# SCH_SrProj_v1_2.net
KiCad netlist of a schematic drawn in EasyEDA
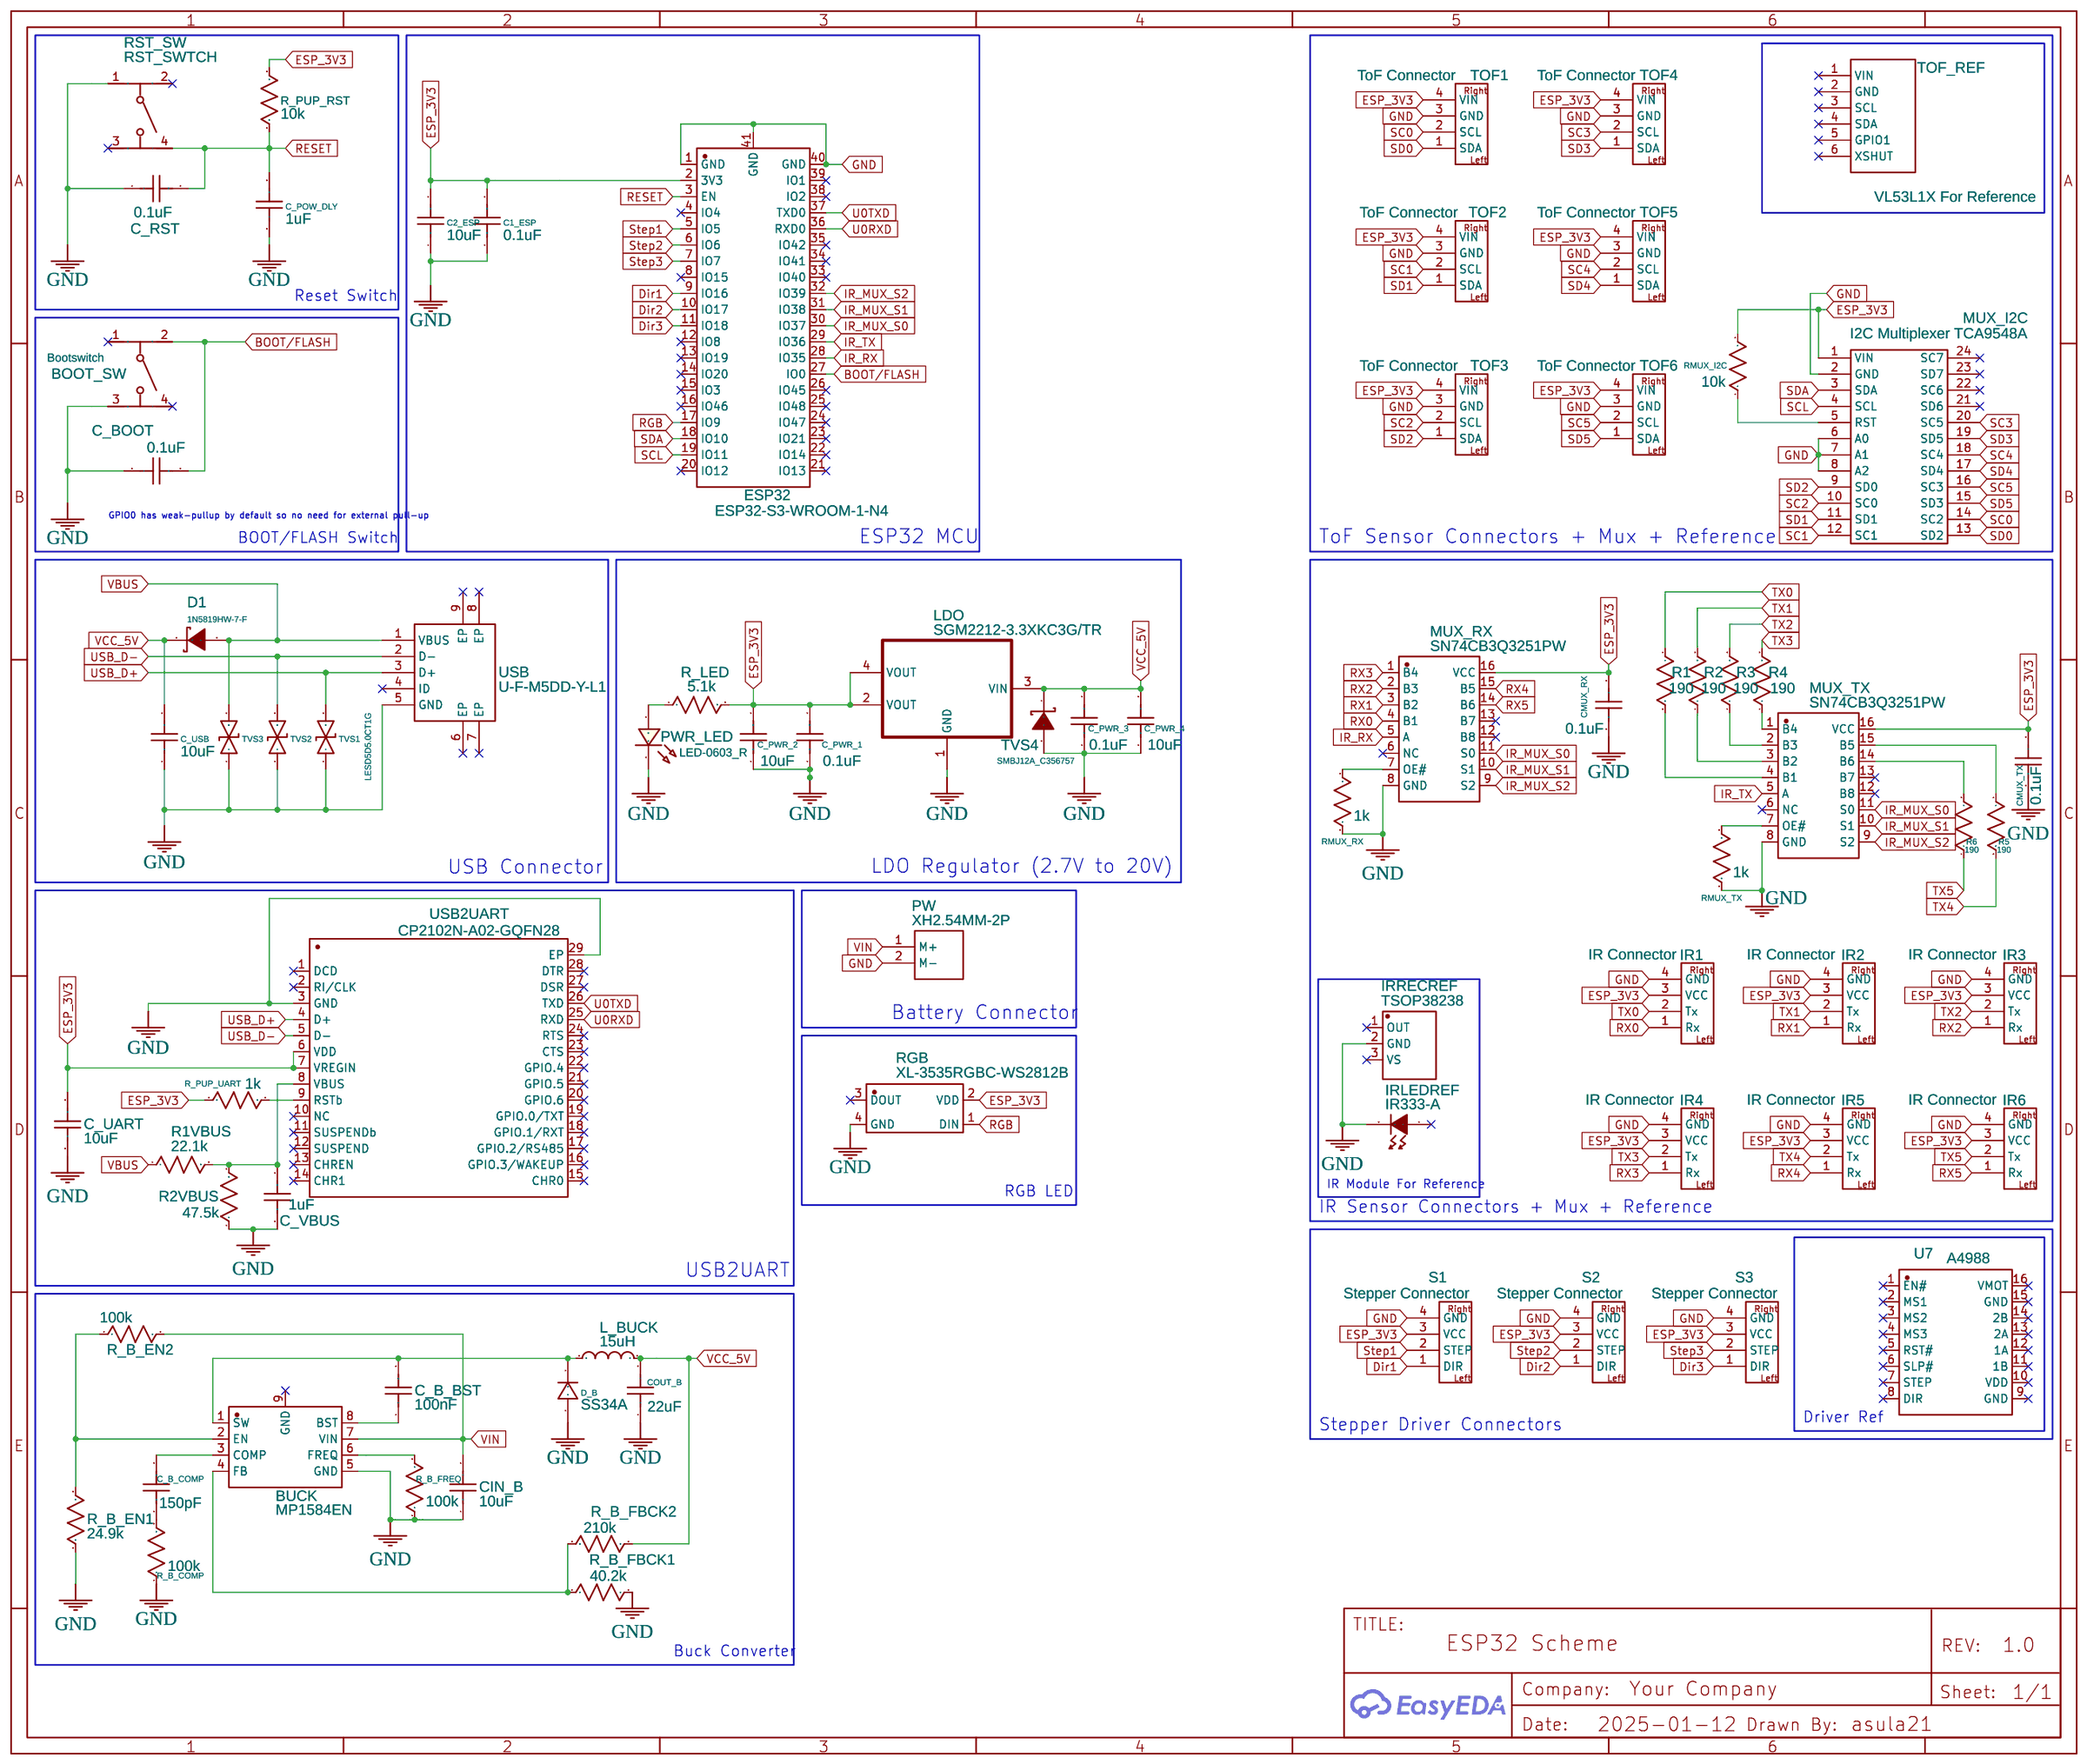
[diagram p0: schematic sheet]

(export (version "E")
  (design (tool "Eeschema 10.0.6"))
  (components
    (comp (ref "BOOT_SW")
      (value "Bootswitch")
      (fields
        (field (name "Manufacturer Part") "Switch,6*6*6Plastic head,260G, 0.25mm,Straight line")
        (field (name "Manufacturer") "BBJ")
      )
      (libsource (lib "") (part "Button-6x6x6mm"))
    )
    (comp (ref "BUCK") (value "MP1584EN") (libsource (lib "") (part "MP1584EN")))
    (comp (ref "C1_ESP") (value "0.1uF") (libsource (lib "") (part "C_0603_US_6")))
    (comp (ref "C2_ESP") (value "10uF") (libsource (lib "") (part "C_0603_US_12")))
    (comp (ref "CIN_B") (value "10uF") (libsource (lib "") (part "C_0603_US_5")))
    (comp (ref "CMUX_RX") (value "0.1uF") (libsource (lib "") (part "C_0603_US_13")))
    (comp (ref "CMUX_TX") (value "0.1uF") (libsource (lib "") (part "C_0603_US_8")))
    (comp (ref "COUT_B") (value "22uF") (libsource (lib "") (part "C_0603_US_4")))
    (comp (ref "C_BOOT") (value "0.1uF") (libsource (lib "") (part "C_0603_US_11")))
    (comp (ref "C_B_BST") (value "100nF") (libsource (lib "") (part "C_0603_US_7")))
    (comp (ref "C_B_COMP") (value "150pF") (libsource (lib "") (part "C_0603_US_9")))
    (comp (ref "C_POW_DLY") (value "1uF") (libsource (lib "") (part "C_0603_US_10")))
    (comp (ref "C_PWR_1") (value "0.1uF") (libsource (lib "") (part "C_0603_US")))
    (comp (ref "C_PWR_2") (value "10uF") (libsource (lib "") (part "C_0603_US")))
    (comp (ref "C_PWR_3") (value "0.1uF") (libsource (lib "") (part "C_0603_US")))
    (comp (ref "C_PWR_4") (value "10uF") (libsource (lib "") (part "C_0603_US")))
    (comp (ref "C_RST") (value "0.1uF") (libsource (lib "") (part "C_0603_US_1")))
    (comp (ref "C_UART") (value "10uF") (libsource (lib "") (part "C_0603_US_2")))
    (comp (ref "C_USB") (value "10uF") (libsource (lib "") (part "C_0603_US_14")))
    (comp (ref "C_VBUS") (value "1uF") (libsource (lib "") (part "C_0603_US_3")))
    (comp (ref "D1")
      (value "1N5819HW-7-F")
      (fields (field (name "Manufacturer") "DIODES(美台)"))
      (libsource (lib "") (part "1N5819HW-7-F"))
    )
    (comp (ref "D_B")
      (value "SS34A")
      (fields (field (name "Manufacturer") "YANGJIE(扬杰)"))
      (libsource (lib "") (part "SS34A"))
    )
    (comp (ref "ESP32")
      (value "ESP32-S3-WROOM-1-N4")
      (fields (field (name "Manufacturer") "ESPRESSIF(乐鑫)"))
      (libsource (lib "") (part "ESP32-S3-WROOM-1-N4"))
    )
    (comp (ref "IR1") (value "IR Connector") (libsource (lib "") (part "MY XH2.54MM.4P_1")))
    (comp (ref "IR2") (value "IR Connector") (libsource (lib "") (part "MY XH2.54MM.4P_1")))
    (comp (ref "IR3") (value "IR Connector") (libsource (lib "") (part "MY XH2.54MM.4P_1")))
    (comp (ref "IR4") (value "IR Connector") (libsource (lib "") (part "MY XH2.54MM.4P_1")))
    (comp (ref "IR5") (value "IR Connector") (libsource (lib "") (part "MY XH2.54MM.4P_1")))
    (comp (ref "IR6") (value "IR Connector") (libsource (lib "") (part "MY XH2.54MM.4P_1")))
    (comp (ref "IRLEDREF")
      (value "IR333-A")
      (fields (field (name "Manufacturer") "EVERLIGHT(亿光)"))
      (libsource (lib "") (part "IR333-A"))
    )
    (comp (ref "IRRECREF")
      (value "TSOP38238")
      (fields (field (name "Manufacturer") "VISHAY(威世)"))
      (libsource (lib "") (part "TSOP38238"))
    )
    (comp (ref "LDO") (value "SGM2212-3.3XKC3G/TR") (libsource (lib "") (part "SGM2212-3.3XKC3G/TR")))
    (comp (ref "L_BUCK")
      (value "15uH")
      (fields (field (name "Manufacturer Part") "CYH127-4.7UH") (field (name "Manufacturer") "SHOU HAN(首韩)"))
      (libsource (lib "") (part "CYH127-4.7UH"))
    )
    (comp (ref "MUX_I2C")
      (value "I2C Multiplexer TCA9548A")
      (fields (field (name "Manufacturer Part") "IDSN-TCA9548A") (field (name "Manufacturer") "IDSN"))
      (libsource (lib "") (part "TCA9548A I2C MULTIPLEXER 8 CHANEL"))
    )
    (comp (ref "MUX_RX")
      (value "SN74CB3Q3251PW")
      (fields (field (name "Manufacturer") "TI(德州仪器)"))
      (libsource (lib "") (part "SN74CB3Q3251PW_1"))
    )
    (comp (ref "MUX_TX")
      (value "SN74CB3Q3251PW")
      (fields (field (name "Manufacturer") "TI(德州仪器)"))
      (libsource (lib "") (part "SN74CB3Q3251PW"))
    )
    (comp (ref "PW")
      (value "XH2.54MM-2P")
      (fields (field (name "Manufacturer Part") "Header P2 PH2.0 TUANLE"))
      (libsource (lib "") (part "PH2.0-2P"))
    )
    (comp (ref "PWR_LED")
      (value "LED-0603_R")
      (fields
        (field (name "Manufacturer Part") "19-217/R6C-AL1M2VY/3T")
        (field (name "Manufacturer") "EVERLIGHT(台湾亿光)")
      )
      (libsource (lib "") (part "LED-0603_R"))
    )
    (comp (ref "R1") (value "190") (libsource (lib "") (part "R_0805_US")))
    (comp (ref "R1VBUS") (value "22.1k") (libsource (lib "") (part "R_0603_US_9")))
    (comp (ref "R2") (value "190") (libsource (lib "") (part "R_0805_US_1")))
    (comp (ref "R2VBUS") (value "47.5k") (libsource (lib "") (part "R_0603_US_12")))
    (comp (ref "R3") (value "190") (libsource (lib "") (part "R_0805_US_1")))
    (comp (ref "R4") (value "190") (libsource (lib "") (part "R_0805_US_1")))
    (comp (ref "R5") (value "190") (libsource (lib "") (part "R_0805_US")))
    (comp (ref "R6") (value "190") (libsource (lib "") (part "R_0805_US_1")))
    (comp (ref "RGB")
      (value "XL-3535RGBC-WS2812B")
      (fields (field (name "Manufacturer") "XINGLIGHT(成兴光)"))
      (libsource (lib "") (part "XL-3535RGBC-WS2812B"))
    )
    (comp (ref "RMUX_I2C") (value "10k") (libsource (lib "") (part "R_0603_US_7")))
    (comp (ref "RMUX_RX") (value "1k") (libsource (lib "") (part "R_0603_US_6")))
    (comp (ref "RMUX_TX") (value "1k") (libsource (lib "") (part "R_0603_US_10")))
    (comp (ref "RST_SW")
      (value "RST_SWTCH")
      (fields
        (field (name "Manufacturer Part") "Switch,6*6*6Plastic head,260G, 0.25mm,Straight line")
        (field (name "Manufacturer") "BBJ")
      )
      (libsource (lib "") (part "Button-6x6x6mm_1"))
    )
    (comp (ref "R_B_COMP") (value "100k") (libsource (lib "") (part "R_0603_US_11")))
    (comp (ref "R_B_EN1") (value "24.9k") (libsource (lib "") (part "R_0603_US_13")))
    (comp (ref "R_B_EN2") (value "100k") (libsource (lib "") (part "R_0603_US_5")))
    (comp (ref "R_B_FBCK1") (value "40.2k") (libsource (lib "") (part "R_0603_US_3")))
    (comp (ref "R_B_FBCK2") (value "210k") (libsource (lib "") (part "R_0603_US_2")))
    (comp (ref "R_B_FREQ") (value "100k") (libsource (lib "") (part "R_0603_US_1")))
    (comp (ref "R_LED") (value "5.1k") (libsource (lib "") (part "R_0603_US_4")))
    (comp (ref "R_PUP_RST") (value "10k") (libsource (lib "") (part "R_0603_US_8")))
    (comp (ref "R_PUP_UART") (value "1k") (libsource (lib "") (part "R_0603_US")))
    (comp (ref "S1") (value "Stepper Connector") (libsource (lib "") (part "MY XH2.54MM.4P_2")))
    (comp (ref "S2") (value "Stepper Connector") (libsource (lib "") (part "MY XH2.54MM.4P_2")))
    (comp (ref "S3") (value "Stepper Connector") (libsource (lib "") (part "MY XH2.54MM.4P_2")))
    (comp (ref "TOF1") (value "ToF Connector") (libsource (lib "") (part "MY XH2.54MM.4P")))
    (comp (ref "TOF2") (value "ToF Connector") (libsource (lib "") (part "MY XH2.54MM.4P")))
    (comp (ref "TOF3") (value "ToF Connector") (libsource (lib "") (part "MY XH2.54MM.4P")))
    (comp (ref "TOF4") (value "ToF Connector") (libsource (lib "") (part "MY XH2.54MM.4P")))
    (comp (ref "TOF5") (value "ToF Connector") (libsource (lib "") (part "MY XH2.54MM.4P")))
    (comp (ref "TOF6") (value "ToF Connector") (libsource (lib "") (part "MY XH2.54MM.4P")))
    (comp (ref "TOF_REF")
      (value "VL53L1X For Reference")
      (fields (field (name "Manufacturer Part") "VL53L0X Time-of-Flight Distance Sensor VL53L0X"))
      (libsource (lib "") (part "VL53L1X_BREAKOUT"))
    )
    (comp (ref "TVS1")
      (value "LESD5D5.0CT1G")
      (fields (field (name "Manufacturer") "LRC(乐山无线电)"))
      (libsource (lib "") (part "LESD5D5.0CT1G"))
    )
    (comp (ref "TVS2")
      (value "LESD5D5.0CT1G")
      (fields (field (name "Manufacturer") "LRC(乐山无线电)"))
      (libsource (lib "") (part "LESD5D5.0CT1G"))
    )
    (comp (ref "TVS3")
      (value "LESD5D5.0CT1G")
      (fields (field (name "Manufacturer") "LRC(乐山无线电)"))
      (libsource (lib "") (part "LESD5D5.0CT1G"))
    )
    (comp (ref "TVS4")
      (value "SMBJ12A_C356757")
      (fields (field (name "Manufacturer Part") "SMBJ12A") (field (name "Manufacturer") "JJW(捷捷微)"))
      (libsource (lib "") (part "SMBJ12A_C356757"))
    )
    (comp (ref "U7") (value "A4988") (libsource (lib "") (part "A4988")))
    (comp (ref "USB")
      (value "U-F-M5DD-Y-L1")
      (fields (field (name "Manufacturer") "韩国韩荣"))
      (libsource (lib "") (part "U-F-M5DD-Y-L1"))
    )
    (comp (ref "USB2UART")
      (value "CP2102N-A02-GQFN28")
      (fields (field (name "Manufacturer") "SKYWORKS/SILICON LABS(芯科)"))
      (libsource (lib "") (part "CP2102N-A02-GQFN28"))
    )
  )
  (nets
    (net (code "1") (name "BOOT{slash}FLASH") (class "Default")
      (node (ref "BOOT_SW") (pin "2") (pinfunction "2_2") (pintype "unspecified"))
      (node (ref "C_BOOT") (pin "2") (pinfunction "2_2") (pintype "unspecified"))
      (node (ref "ESP32") (pin "27") (pinfunction "IO0_27") (pintype "unspecified"))
    )
    (net (code "2") (name "Dir1") (class "Default")
      (node (ref "ESP32") (pin "9") (pinfunction "IO16_9") (pintype "unspecified"))
      (node (ref "S1") (pin "1") (pinfunction "DIR_1") (pintype "unspecified"))
    )
    (net (code "3") (name "Dir2") (class "Default")
      (node (ref "ESP32") (pin "10") (pinfunction "IO17_10") (pintype "unspecified"))
      (node (ref "S2") (pin "1") (pinfunction "DIR_1") (pintype "unspecified"))
    )
    (net (code "4") (name "Dir3") (class "Default")
      (node (ref "ESP32") (pin "11") (pinfunction "IO18_11") (pintype "unspecified"))
      (node (ref "S3") (pin "1") (pinfunction "DIR_1") (pintype "unspecified"))
    )
    (net (code "5") (name "ESP_3V3") (class "Default")
      (node (ref "C1_ESP") (pin "2") (pinfunction "2_2") (pintype "unspecified"))
      (node (ref "C2_ESP") (pin "2") (pinfunction "2_2") (pintype "unspecified"))
      (node (ref "CMUX_RX") (pin "2") (pinfunction "2_2") (pintype "unspecified"))
      (node (ref "CMUX_TX") (pin "2") (pinfunction "2_2") (pintype "unspecified"))
      (node (ref "C_PWR_1") (pin "2") (pinfunction "2_2") (pintype "unspecified"))
      (node (ref "C_PWR_2") (pin "2") (pinfunction "2_2") (pintype "unspecified"))
      (node (ref "C_UART") (pin "2") (pinfunction "2_2") (pintype "unspecified"))
      (node (ref "ESP32") (pin "2") (pinfunction "3V3_2") (pintype "unspecified"))
      (node (ref "IR1") (pin "3") (pinfunction "VCC_3") (pintype "unspecified"))
      (node (ref "IR2") (pin "3") (pinfunction "VCC_3") (pintype "unspecified"))
      (node (ref "IR3") (pin "3") (pinfunction "VCC_3") (pintype "unspecified"))
      (node (ref "IR4") (pin "3") (pinfunction "VCC_3") (pintype "unspecified"))
      (node (ref "IR5") (pin "3") (pinfunction "VCC_3") (pintype "unspecified"))
      (node (ref "IR6") (pin "3") (pinfunction "VCC_3") (pintype "unspecified"))
      (node (ref "LDO") (pin "2") (pinfunction "VOUT_2") (pintype "unspecified"))
      (node (ref "LDO") (pin "4") (pinfunction "VOUT_4") (pintype "unspecified"))
      (node (ref "MUX_I2C") (pin "1") (pinfunction "VIN_1") (pintype "unspecified"))
      (node (ref "MUX_RX") (pin "16") (pinfunction "VCC_16") (pintype "unspecified"))
      (node (ref "MUX_TX") (pin "16") (pinfunction "VCC_16") (pintype "unspecified"))
      (node (ref "RGB") (pin "2") (pinfunction "VDD_2") (pintype "unspecified"))
      (node (ref "RMUX_I2C") (pin "2") (pinfunction "2_2") (pintype "unspecified"))
      (node (ref "R_LED") (pin "2") (pinfunction "2_2") (pintype "unspecified"))
      (node (ref "R_PUP_RST") (pin "2") (pinfunction "2_2") (pintype "unspecified"))
      (node (ref "R_PUP_UART") (pin "2") (pinfunction "2_2") (pintype "unspecified"))
      (node (ref "S1") (pin "3") (pinfunction "VCC_3") (pintype "unspecified"))
      (node (ref "S2") (pin "3") (pinfunction "VCC_3") (pintype "unspecified"))
      (node (ref "S3") (pin "3") (pinfunction "VCC_3") (pintype "unspecified"))
      (node (ref "TOF1") (pin "4") (pinfunction "VIN_4") (pintype "unspecified"))
      (node (ref "TOF2") (pin "4") (pinfunction "VIN_4") (pintype "unspecified"))
      (node (ref "TOF3") (pin "4") (pinfunction "VIN_4") (pintype "unspecified"))
      (node (ref "TOF4") (pin "4") (pinfunction "VIN_4") (pintype "unspecified"))
      (node (ref "TOF5") (pin "4") (pinfunction "VIN_4") (pintype "unspecified"))
      (node (ref "TOF6") (pin "4") (pinfunction "VIN_4") (pintype "unspecified"))
      (node (ref "USB2UART") (pin "6") (pinfunction "VDD_6") (pintype "unspecified"))
      (node (ref "USB2UART") (pin "7") (pinfunction "VREGIN_7") (pintype "unspecified"))
    )
    (net (code "6") (name "GND") (class "Default")
      (node (ref "BOOT_SW") (pin "3") (pinfunction "3_3") (pintype "unspecified"))
      (node (ref "BUCK") (pin "5") (pinfunction "GND_5") (pintype "unspecified"))
      (node (ref "C1_ESP") (pin "1") (pinfunction "1_1") (pintype "unspecified"))
      (node (ref "C2_ESP") (pin "1") (pinfunction "1_1") (pintype "unspecified"))
      (node (ref "CIN_B") (pin "1") (pinfunction "1_1") (pintype "unspecified"))
      (node (ref "CMUX_RX") (pin "1") (pinfunction "1_1") (pintype "unspecified"))
      (node (ref "CMUX_TX") (pin "1") (pinfunction "1_1") (pintype "unspecified"))
      (node (ref "COUT_B") (pin "1") (pinfunction "1_1") (pintype "unspecified"))
      (node (ref "C_BOOT") (pin "1") (pinfunction "1_1") (pintype "unspecified"))
      (node (ref "C_POW_DLY") (pin "1") (pinfunction "1_1") (pintype "unspecified"))
      (node (ref "C_PWR_1") (pin "1") (pinfunction "1_1") (pintype "unspecified"))
      (node (ref "C_PWR_2") (pin "1") (pinfunction "1_1") (pintype "unspecified"))
      (node (ref "C_PWR_3") (pin "1") (pinfunction "1_1") (pintype "unspecified"))
      (node (ref "C_PWR_4") (pin "1") (pinfunction "1_1") (pintype "unspecified"))
      (node (ref "C_RST") (pin "1") (pinfunction "1_1") (pintype "unspecified"))
      (node (ref "C_UART") (pin "1") (pinfunction "1_1") (pintype "unspecified"))
      (node (ref "C_USB") (pin "1") (pinfunction "1_1") (pintype "unspecified"))
      (node (ref "C_VBUS") (pin "2") (pinfunction "2_2") (pintype "unspecified"))
      (node (ref "D_B") (pin "2") (pinfunction "A_2") (pintype "unspecified"))
      (node (ref "ESP32") (pin "1") (pinfunction "GND_1") (pintype "unspecified"))
      (node (ref "ESP32") (pin "40") (pinfunction "GND_40") (pintype "unspecified"))
      (node (ref "ESP32") (pin "41") (pinfunction "GND_41") (pintype "unspecified"))
      (node (ref "IR1") (pin "4") (pinfunction "GND_4") (pintype "unspecified"))
      (node (ref "IR2") (pin "4") (pinfunction "GND_4") (pintype "unspecified"))
      (node (ref "IR3") (pin "4") (pinfunction "GND_4") (pintype "unspecified"))
      (node (ref "IR4") (pin "4") (pinfunction "GND_4") (pintype "unspecified"))
      (node (ref "IR5") (pin "4") (pinfunction "GND_4") (pintype "unspecified"))
      (node (ref "IR6") (pin "4") (pinfunction "GND_4") (pintype "unspecified"))
      (node (ref "IRLEDREF") (pin "2") (pinfunction "C_2") (pintype "input"))
      (node (ref "IRRECREF") (pin "2") (pinfunction "GND_2") (pintype "unspecified"))
      (node (ref "LDO") (pin "1") (pinfunction "GND_1") (pintype "unspecified"))
      (node (ref "MUX_I2C") (pin "2") (pinfunction "GND_2") (pintype "unspecified"))
      (node (ref "MUX_I2C") (pin "6") (pinfunction "A0_6") (pintype "unspecified"))
      (node (ref "MUX_I2C") (pin "7") (pinfunction "A1_7") (pintype "unspecified"))
      (node (ref "MUX_I2C") (pin "8") (pinfunction "A2_8") (pintype "unspecified"))
      (node (ref "MUX_RX") (pin "8") (pinfunction "GND_8") (pintype "unspecified"))
      (node (ref "MUX_TX") (pin "8") (pinfunction "GND_8") (pintype "unspecified"))
      (node (ref "PW") (pin "2") (pinfunction "M-_2") (pintype "unspecified"))
      (node (ref "PWR_LED") (pin "2") (pinfunction "2_2") (pintype "unspecified"))
      (node (ref "R2VBUS") (pin "1") (pinfunction "1_1") (pintype "unspecified"))
      (node (ref "RGB") (pin "4") (pinfunction "GND_4") (pintype "unspecified"))
      (node (ref "RMUX_RX") (pin "1") (pinfunction "1_1") (pintype "unspecified"))
      (node (ref "RMUX_TX") (pin "1") (pinfunction "1_1") (pintype "unspecified"))
      (node (ref "RST_SW") (pin "1") (pinfunction "1_1") (pintype "unspecified"))
      (node (ref "R_B_COMP") (pin "1") (pinfunction "1_1") (pintype "unspecified"))
      (node (ref "R_B_EN1") (pin "1") (pinfunction "1_1") (pintype "unspecified"))
      (node (ref "R_B_FBCK1") (pin "2") (pinfunction "2_2") (pintype "unspecified"))
      (node (ref "R_B_FREQ") (pin "1") (pinfunction "1_1") (pintype "unspecified"))
      (node (ref "S1") (pin "4") (pinfunction "GND_4") (pintype "unspecified"))
      (node (ref "S2") (pin "4") (pinfunction "GND_4") (pintype "unspecified"))
      (node (ref "S3") (pin "4") (pinfunction "GND_4") (pintype "unspecified"))
      (node (ref "TOF1") (pin "3") (pinfunction "GND_3") (pintype "unspecified"))
      (node (ref "TOF2") (pin "3") (pinfunction "GND_3") (pintype "unspecified"))
      (node (ref "TOF3") (pin "3") (pinfunction "GND_3") (pintype "unspecified"))
      (node (ref "TOF4") (pin "3") (pinfunction "GND_3") (pintype "unspecified"))
      (node (ref "TOF5") (pin "3") (pinfunction "GND_3") (pintype "unspecified"))
      (node (ref "TOF6") (pin "3") (pinfunction "GND_3") (pintype "unspecified"))
      (node (ref "TVS1") (pin "1") (pinfunction "1_1") (pintype "unspecified"))
      (node (ref "TVS2") (pin "1") (pinfunction "1_1") (pintype "unspecified"))
      (node (ref "TVS3") (pin "1") (pinfunction "1_1") (pintype "unspecified"))
      (node (ref "TVS4") (pin "2") (pinfunction "A_2") (pintype "unspecified"))
      (node (ref "USB") (pin "5") (pinfunction "GND_5") (pintype "unspecified"))
      (node (ref "USB2UART") (pin "29") (pinfunction "EP_29") (pintype "unspecified"))
      (node (ref "USB2UART") (pin "3") (pinfunction "GND_3") (pintype "unspecified"))
    )
    (net (code "7") (name "IR_MUX_S0") (class "Default")
      (node (ref "ESP32") (pin "30") (pinfunction "IO37_30") (pintype "unspecified"))
      (node (ref "MUX_RX") (pin "11") (pinfunction "S0_11") (pintype "unspecified"))
      (node (ref "MUX_TX") (pin "11") (pinfunction "S0_11") (pintype "unspecified"))
    )
    (net (code "8") (name "IR_MUX_S1") (class "Default")
      (node (ref "ESP32") (pin "31") (pinfunction "IO38_31") (pintype "unspecified"))
      (node (ref "MUX_RX") (pin "10") (pinfunction "S1_10") (pintype "unspecified"))
      (node (ref "MUX_TX") (pin "10") (pinfunction "S1_10") (pintype "unspecified"))
    )
    (net (code "9") (name "IR_MUX_S2") (class "Default")
      (node (ref "ESP32") (pin "32") (pinfunction "IO39_32") (pintype "unspecified"))
      (node (ref "MUX_RX") (pin "9") (pinfunction "S2_9") (pintype "unspecified"))
      (node (ref "MUX_TX") (pin "9") (pinfunction "S2_9") (pintype "unspecified"))
    )
    (net (code "10") (name "IR_RX") (class "Default")
      (node (ref "ESP32") (pin "28") (pinfunction "IO35_28") (pintype "unspecified"))
      (node (ref "MUX_RX") (pin "5") (pinfunction "A_5") (pintype "unspecified"))
    )
    (net (code "11") (name "IR_TX") (class "Default")
      (node (ref "ESP32") (pin "29") (pinfunction "IO36_29") (pintype "unspecified"))
      (node (ref "MUX_TX") (pin "5") (pinfunction "A_5") (pintype "unspecified"))
    )
    (net (code "12") (name "Net-(BUCK-BST)") (class "Default")
      (node (ref "BUCK") (pin "8") (pinfunction "BST_8") (pintype "unspecified"))
      (node (ref "C_B_BST") (pin "1") (pinfunction "1_1") (pintype "unspecified"))
    )
    (net (code "13") (name "Net-(BUCK-COMP)") (class "Default")
      (node (ref "BUCK") (pin "3") (pinfunction "COMP_3") (pintype "unspecified"))
      (node (ref "C_B_COMP") (pin "2") (pinfunction "2_2") (pintype "unspecified"))
    )
    (net (code "14") (name "Net-(BUCK-EN)") (class "Default")
      (node (ref "BUCK") (pin "2") (pinfunction "EN_2") (pintype "unspecified"))
      (node (ref "R_B_EN1") (pin "2") (pinfunction "2_2") (pintype "unspecified"))
      (node (ref "R_B_EN2") (pin "1") (pinfunction "1_1") (pintype "unspecified"))
    )
    (net (code "15") (name "Net-(BUCK-FB)") (class "Default")
      (node (ref "BUCK") (pin "4") (pinfunction "FB_4") (pintype "unspecified"))
      (node (ref "R_B_FBCK1") (pin "1") (pinfunction "1_1") (pintype "unspecified"))
      (node (ref "R_B_FBCK2") (pin "2") (pinfunction "2_2") (pintype "unspecified"))
    )
    (net (code "16") (name "Net-(BUCK-FREQ)") (class "Default")
      (node (ref "BUCK") (pin "6") (pinfunction "FREQ_6") (pintype "unspecified"))
      (node (ref "R_B_FREQ") (pin "2") (pinfunction "2_2") (pintype "unspecified"))
    )
    (net (code "17") (name "Net-(BUCK-SW)") (class "Default")
      (node (ref "BUCK") (pin "1") (pinfunction "SW_1") (pintype "unspecified"))
      (node (ref "C_B_BST") (pin "2") (pinfunction "2_2") (pintype "unspecified"))
      (node (ref "D_B") (pin "1") (pinfunction "C_1") (pintype "unspecified"))
      (node (ref "L_BUCK") (pin "1") (pinfunction "1_1") (pintype "unspecified"))
    )
    (net (code "18") (name "Net-(C_B_COMP-Pad1)") (class "Default")
      (node (ref "C_B_COMP") (pin "1") (pinfunction "1_1") (pintype "unspecified"))
      (node (ref "R_B_COMP") (pin "2") (pinfunction "2_2") (pintype "unspecified"))
    )
    (net (code "19") (name "Net-(MUX_I2C-RST)") (class "Default")
      (node (ref "MUX_I2C") (pin "5") (pinfunction "RST_5") (pintype "unspecified"))
      (node (ref "RMUX_I2C") (pin "1") (pinfunction "1_1") (pintype "unspecified"))
    )
    (net (code "20") (name "Net-(MUX_RX-OE#)") (class "Default")
      (node (ref "MUX_RX") (pin "7") (pinfunction "OE#_7") (pintype "unspecified"))
      (node (ref "RMUX_RX") (pin "2") (pinfunction "2_2") (pintype "unspecified"))
    )
    (net (code "21") (name "Net-(MUX_TX-B1)") (class "Default")
      (node (ref "MUX_TX") (pin "4") (pinfunction "B1_4") (pintype "unspecified"))
      (node (ref "R1") (pin "2") (pinfunction "2_2") (pintype "unspecified"))
    )
    (net (code "22") (name "Net-(MUX_TX-B2)") (class "Default")
      (node (ref "MUX_TX") (pin "3") (pinfunction "B2_3") (pintype "unspecified"))
      (node (ref "R2") (pin "1") (pinfunction "1_1") (pintype "unspecified"))
    )
    (net (code "23") (name "Net-(MUX_TX-B3)") (class "Default")
      (node (ref "MUX_TX") (pin "2") (pinfunction "B3_2") (pintype "unspecified"))
      (node (ref "R3") (pin "1") (pinfunction "1_1") (pintype "unspecified"))
    )
    (net (code "24") (name "Net-(MUX_TX-B4)") (class "Default")
      (node (ref "MUX_TX") (pin "1") (pinfunction "B4_1") (pintype "unspecified"))
      (node (ref "R4") (pin "1") (pinfunction "1_1") (pintype "unspecified"))
    )
    (net (code "25") (name "Net-(MUX_TX-B5)") (class "Default")
      (node (ref "MUX_TX") (pin "15") (pinfunction "B5_15") (pintype "unspecified"))
      (node (ref "R5") (pin "1") (pinfunction "1_1") (pintype "unspecified"))
    )
    (net (code "26") (name "Net-(MUX_TX-B6)") (class "Default")
      (node (ref "MUX_TX") (pin "14") (pinfunction "B6_14") (pintype "unspecified"))
      (node (ref "R6") (pin "2") (pinfunction "2_2") (pintype "unspecified"))
    )
    (net (code "27") (name "Net-(MUX_TX-OE#)") (class "Default")
      (node (ref "MUX_TX") (pin "7") (pinfunction "OE#_7") (pintype "unspecified"))
      (node (ref "RMUX_TX") (pin "2") (pinfunction "2_2") (pintype "unspecified"))
    )
    (net (code "28") (name "Net-(PWR_LED-Pad1)") (class "Default")
      (node (ref "PWR_LED") (pin "1") (pinfunction "1_1") (pintype "unspecified"))
      (node (ref "R_LED") (pin "1") (pinfunction "1_1") (pintype "unspecified"))
    )
    (net (code "29") (name "Net-(USB2UART-RSTb)") (class "Default")
      (node (ref "R_PUP_UART") (pin "1") (pinfunction "1_1") (pintype "unspecified"))
      (node (ref "USB2UART") (pin "9") (pinfunction "RSTb_9") (pintype "unspecified"))
    )
    (net (code "30") (name "Net-(USB2UART-VBUS)") (class "Default")
      (node (ref "C_VBUS") (pin "1") (pinfunction "1_1") (pintype "unspecified"))
      (node (ref "R1VBUS") (pin "2") (pinfunction "2_2") (pintype "unspecified"))
      (node (ref "R2VBUS") (pin "2") (pinfunction "2_2") (pintype "unspecified"))
      (node (ref "USB2UART") (pin "8") (pinfunction "VBUS_8") (pintype "unspecified"))
    )
    (net (code "31") (name "RESET") (class "Default")
      (node (ref "C_POW_DLY") (pin "2") (pinfunction "2_2") (pintype "unspecified"))
      (node (ref "C_RST") (pin "2") (pinfunction "2_2") (pintype "unspecified"))
      (node (ref "ESP32") (pin "3") (pinfunction "EN_3") (pintype "unspecified"))
      (node (ref "RST_SW") (pin "4") (pinfunction "4_4") (pintype "unspecified"))
      (node (ref "R_PUP_RST") (pin "1") (pinfunction "1_1") (pintype "unspecified"))
    )
    (net (code "32") (name "RGB") (class "Default")
      (node (ref "ESP32") (pin "17") (pinfunction "IO9_17") (pintype "unspecified"))
      (node (ref "RGB") (pin "1") (pinfunction "DIN_1") (pintype "unspecified"))
    )
    (net (code "33") (name "RX0") (class "Default")
      (node (ref "IR1") (pin "1") (pinfunction "Rx_1") (pintype "unspecified"))
      (node (ref "MUX_RX") (pin "4") (pinfunction "B1_4") (pintype "unspecified"))
    )
    (net (code "34") (name "RX1") (class "Default")
      (node (ref "IR2") (pin "1") (pinfunction "Rx_1") (pintype "unspecified"))
      (node (ref "MUX_RX") (pin "3") (pinfunction "B2_3") (pintype "unspecified"))
    )
    (net (code "35") (name "RX2") (class "Default")
      (node (ref "IR3") (pin "1") (pinfunction "Rx_1") (pintype "unspecified"))
      (node (ref "MUX_RX") (pin "2") (pinfunction "B3_2") (pintype "unspecified"))
    )
    (net (code "36") (name "RX3") (class "Default")
      (node (ref "IR4") (pin "1") (pinfunction "Rx_1") (pintype "unspecified"))
      (node (ref "MUX_RX") (pin "1") (pinfunction "B4_1") (pintype "unspecified"))
    )
    (net (code "37") (name "RX4") (class "Default")
      (node (ref "IR5") (pin "1") (pinfunction "Rx_1") (pintype "unspecified"))
      (node (ref "MUX_RX") (pin "15") (pinfunction "B5_15") (pintype "unspecified"))
    )
    (net (code "38") (name "RX5") (class "Default")
      (node (ref "IR6") (pin "1") (pinfunction "Rx_1") (pintype "unspecified"))
      (node (ref "MUX_RX") (pin "14") (pinfunction "B6_14") (pintype "unspecified"))
    )
    (net (code "39") (name "SC0") (class "Default")
      (node (ref "MUX_I2C") (pin "14") (pinfunction "SC2_14") (pintype "unspecified"))
      (node (ref "TOF1") (pin "2") (pinfunction "SCL_2") (pintype "unspecified"))
    )
    (net (code "40") (name "SC1") (class "Default")
      (node (ref "MUX_I2C") (pin "12") (pinfunction "SC1_12") (pintype "unspecified"))
      (node (ref "TOF2") (pin "2") (pinfunction "SCL_2") (pintype "unspecified"))
    )
    (net (code "41") (name "SC2") (class "Default")
      (node (ref "MUX_I2C") (pin "10") (pinfunction "SC0_10") (pintype "unspecified"))
      (node (ref "TOF3") (pin "2") (pinfunction "SCL_2") (pintype "unspecified"))
    )
    (net (code "42") (name "SC3") (class "Default")
      (node (ref "MUX_I2C") (pin "20") (pinfunction "SC5_20") (pintype "unspecified"))
      (node (ref "TOF4") (pin "2") (pinfunction "SCL_2") (pintype "unspecified"))
    )
    (net (code "43") (name "SC4") (class "Default")
      (node (ref "MUX_I2C") (pin "18") (pinfunction "SC4_18") (pintype "unspecified"))
      (node (ref "TOF5") (pin "2") (pinfunction "SCL_2") (pintype "unspecified"))
    )
    (net (code "44") (name "SC5") (class "Default")
      (node (ref "MUX_I2C") (pin "16") (pinfunction "SC3_16") (pintype "unspecified"))
      (node (ref "TOF6") (pin "2") (pinfunction "SCL_2") (pintype "unspecified"))
    )
    (net (code "45") (name "SCL") (class "Default")
      (node (ref "ESP32") (pin "19") (pinfunction "IO11_19") (pintype "unspecified"))
      (node (ref "MUX_I2C") (pin "4") (pinfunction "SCL_4") (pintype "unspecified"))
    )
    (net (code "46") (name "SD0") (class "Default")
      (node (ref "MUX_I2C") (pin "13") (pinfunction "SD2_13") (pintype "unspecified"))
      (node (ref "TOF1") (pin "1") (pinfunction "SDA_1") (pintype "unspecified"))
    )
    (net (code "47") (name "SD1") (class "Default")
      (node (ref "MUX_I2C") (pin "11") (pinfunction "SD1_11") (pintype "unspecified"))
      (node (ref "TOF2") (pin "1") (pinfunction "SDA_1") (pintype "unspecified"))
    )
    (net (code "48") (name "SD2") (class "Default")
      (node (ref "MUX_I2C") (pin "9") (pinfunction "SD0_9") (pintype "unspecified"))
      (node (ref "TOF3") (pin "1") (pinfunction "SDA_1") (pintype "unspecified"))
    )
    (net (code "49") (name "SD3") (class "Default")
      (node (ref "MUX_I2C") (pin "19") (pinfunction "SD5_19") (pintype "unspecified"))
      (node (ref "TOF4") (pin "1") (pinfunction "SDA_1") (pintype "unspecified"))
    )
    (net (code "50") (name "SD4") (class "Default")
      (node (ref "MUX_I2C") (pin "17") (pinfunction "SD4_17") (pintype "unspecified"))
      (node (ref "TOF5") (pin "1") (pinfunction "SDA_1") (pintype "unspecified"))
    )
    (net (code "51") (name "SD5") (class "Default")
      (node (ref "MUX_I2C") (pin "15") (pinfunction "SD3_15") (pintype "unspecified"))
      (node (ref "TOF6") (pin "1") (pinfunction "SDA_1") (pintype "unspecified"))
    )
    (net (code "52") (name "SDA") (class "Default")
      (node (ref "ESP32") (pin "18") (pinfunction "IO10_18") (pintype "unspecified"))
      (node (ref "MUX_I2C") (pin "3") (pinfunction "SDA_3") (pintype "unspecified"))
    )
    (net (code "53") (name "Step1") (class "Default")
      (node (ref "ESP32") (pin "5") (pinfunction "IO5_5") (pintype "unspecified"))
      (node (ref "S1") (pin "2") (pinfunction "STEP_2") (pintype "unspecified"))
    )
    (net (code "54") (name "Step2") (class "Default")
      (node (ref "ESP32") (pin "6") (pinfunction "IO6_6") (pintype "unspecified"))
      (node (ref "S2") (pin "2") (pinfunction "STEP_2") (pintype "unspecified"))
    )
    (net (code "55") (name "Step3") (class "Default")
      (node (ref "ESP32") (pin "7") (pinfunction "IO7_7") (pintype "unspecified"))
      (node (ref "S3") (pin "2") (pinfunction "STEP_2") (pintype "unspecified"))
    )
    (net (code "56") (name "TX0") (class "Default")
      (node (ref "IR1") (pin "2") (pinfunction "Tx_2") (pintype "unspecified"))
      (node (ref "R1") (pin "1") (pinfunction "1_1") (pintype "unspecified"))
    )
    (net (code "57") (name "TX1") (class "Default")
      (node (ref "IR2") (pin "2") (pinfunction "Tx_2") (pintype "unspecified"))
      (node (ref "R2") (pin "2") (pinfunction "2_2") (pintype "unspecified"))
    )
    (net (code "58") (name "TX2") (class "Default")
      (node (ref "IR3") (pin "2") (pinfunction "Tx_2") (pintype "unspecified"))
      (node (ref "R3") (pin "2") (pinfunction "2_2") (pintype "unspecified"))
    )
    (net (code "59") (name "TX3") (class "Default")
      (node (ref "IR4") (pin "2") (pinfunction "Tx_2") (pintype "unspecified"))
      (node (ref "R4") (pin "2") (pinfunction "2_2") (pintype "unspecified"))
    )
    (net (code "60") (name "TX4") (class "Default")
      (node (ref "IR5") (pin "2") (pinfunction "Tx_2") (pintype "unspecified"))
      (node (ref "R5") (pin "2") (pinfunction "2_2") (pintype "unspecified"))
    )
    (net (code "61") (name "TX5") (class "Default")
      (node (ref "IR6") (pin "2") (pinfunction "Tx_2") (pintype "unspecified"))
      (node (ref "R6") (pin "1") (pinfunction "1_1") (pintype "unspecified"))
    )
    (net (code "62") (name "U0RXD") (class "Default")
      (node (ref "ESP32") (pin "36") (pinfunction "RXD0_36") (pintype "unspecified"))
      (node (ref "USB2UART") (pin "25") (pinfunction "RXD_25") (pintype "unspecified"))
    )
    (net (code "63") (name "U0TXD") (class "Default")
      (node (ref "ESP32") (pin "37") (pinfunction "TXD0_37") (pintype "unspecified"))
      (node (ref "USB2UART") (pin "26") (pinfunction "TXD_26") (pintype "unspecified"))
    )
    (net (code "64") (name "USB_D+") (class "Default")
      (node (ref "TVS1") (pin "2") (pinfunction "2_2") (pintype "unspecified"))
      (node (ref "USB") (pin "3") (pinfunction "D+_3") (pintype "unspecified"))
      (node (ref "USB2UART") (pin "4") (pinfunction "D+_4") (pintype "unspecified"))
    )
    (net (code "65") (name "USB_D-") (class "Default")
      (node (ref "TVS2") (pin "2") (pinfunction "2_2") (pintype "unspecified"))
      (node (ref "USB") (pin "2") (pinfunction "D-_2") (pintype "unspecified"))
      (node (ref "USB2UART") (pin "5") (pinfunction "D-_5") (pintype "unspecified"))
    )
    (net (code "66") (name "VBUS") (class "Default")
      (node (ref "D1") (pin "2") (pinfunction "A_2") (pintype "unspecified"))
      (node (ref "R1VBUS") (pin "1") (pinfunction "1_1") (pintype "unspecified"))
      (node (ref "TVS3") (pin "2") (pinfunction "2_2") (pintype "unspecified"))
      (node (ref "USB") (pin "1") (pinfunction "VBUS_1") (pintype "unspecified"))
    )
    (net (code "67") (name "VCC_5V") (class "Default")
      (node (ref "COUT_B") (pin "2") (pinfunction "2_2") (pintype "unspecified"))
      (node (ref "C_PWR_3") (pin "2") (pinfunction "2_2") (pintype "unspecified"))
      (node (ref "C_PWR_4") (pin "2") (pinfunction "2_2") (pintype "unspecified"))
      (node (ref "C_USB") (pin "2") (pinfunction "2_2") (pintype "unspecified"))
      (node (ref "D1") (pin "1") (pinfunction "K_1") (pintype "unspecified"))
      (node (ref "LDO") (pin "3") (pinfunction "VIN_3") (pintype "unspecified"))
      (node (ref "L_BUCK") (pin "2") (pinfunction "2_2") (pintype "unspecified"))
      (node (ref "R_B_FBCK2") (pin "1") (pinfunction "1_1") (pintype "unspecified"))
      (node (ref "TVS4") (pin "1") (pinfunction "K_1") (pintype "unspecified"))
    )
    (net (code "68") (name "VIN") (class "Default")
      (node (ref "BUCK") (pin "7") (pinfunction "VIN_7") (pintype "unspecified"))
      (node (ref "CIN_B") (pin "2") (pinfunction "2_2") (pintype "unspecified"))
      (node (ref "PW") (pin "1") (pinfunction "M+_1") (pintype "unspecified"))
      (node (ref "R_B_EN2") (pin "2") (pinfunction "2_2") (pintype "unspecified"))
    )
    (net (code "69") (name "unconnected-(BOOT_SW-Pad1)") (class "Default")
      (node (ref "BOOT_SW") (pin "1") (pinfunction "1_1") (pintype "unspecified+no_connect"))
    )
    (net (code "70") (name "unconnected-(BOOT_SW-Pad4)") (class "Default")
      (node (ref "BOOT_SW") (pin "4") (pinfunction "4_4") (pintype "unspecified+no_connect"))
    )
    (net (code "71") (name "unconnected-(BUCK-GND-Pad9)") (class "Default")
      (node (ref "BUCK") (pin "9") (pinfunction "GND_9") (pintype "unspecified+no_connect"))
    )
    (net (code "72") (name "unconnected-(ESP32-IO1-Pad39)") (class "Default")
      (node (ref "ESP32") (pin "39") (pinfunction "IO1_39") (pintype "unspecified+no_connect"))
    )
    (net (code "73") (name "unconnected-(ESP32-IO2-Pad38)") (class "Default")
      (node (ref "ESP32") (pin "38") (pinfunction "IO2_38") (pintype "unspecified+no_connect"))
    )
    (net (code "74") (name "unconnected-(ESP32-IO3-Pad15)") (class "Default")
      (node (ref "ESP32") (pin "15") (pinfunction "IO3_15") (pintype "unspecified+no_connect"))
    )
    (net (code "75") (name "unconnected-(ESP32-IO4-Pad4)") (class "Default")
      (node (ref "ESP32") (pin "4") (pinfunction "IO4_4") (pintype "unspecified+no_connect"))
    )
    (net (code "76") (name "unconnected-(ESP32-IO8-Pad12)") (class "Default")
      (node (ref "ESP32") (pin "12") (pinfunction "IO8_12") (pintype "unspecified+no_connect"))
    )
    (net (code "77") (name "unconnected-(ESP32-IO12-Pad20)") (class "Default")
      (node (ref "ESP32") (pin "20") (pinfunction "IO12_20") (pintype "unspecified+no_connect"))
    )
    (net (code "78") (name "unconnected-(ESP32-IO13-Pad21)") (class "Default")
      (node (ref "ESP32") (pin "21") (pinfunction "IO13_21") (pintype "unspecified+no_connect"))
    )
    (net (code "79") (name "unconnected-(ESP32-IO14-Pad22)") (class "Default")
      (node (ref "ESP32") (pin "22") (pinfunction "IO14_22") (pintype "unspecified+no_connect"))
    )
    (net (code "80") (name "unconnected-(ESP32-IO15-Pad8)") (class "Default")
      (node (ref "ESP32") (pin "8") (pinfunction "IO15_8") (pintype "unspecified+no_connect"))
    )
    (net (code "81") (name "unconnected-(ESP32-IO19-Pad13)") (class "Default")
      (node (ref "ESP32") (pin "13") (pinfunction "IO19_13") (pintype "unspecified+no_connect"))
    )
    (net (code "82") (name "unconnected-(ESP32-IO20-Pad14)") (class "Default")
      (node (ref "ESP32") (pin "14") (pinfunction "IO20_14") (pintype "unspecified+no_connect"))
    )
    (net (code "83") (name "unconnected-(ESP32-IO21-Pad23)") (class "Default")
      (node (ref "ESP32") (pin "23") (pinfunction "IO21_23") (pintype "unspecified+no_connect"))
    )
    (net (code "84") (name "unconnected-(ESP32-IO40-Pad33)") (class "Default")
      (node (ref "ESP32") (pin "33") (pinfunction "IO40_33") (pintype "unspecified+no_connect"))
    )
    (net (code "85") (name "unconnected-(ESP32-IO41-Pad34)") (class "Default")
      (node (ref "ESP32") (pin "34") (pinfunction "IO41_34") (pintype "unspecified+no_connect"))
    )
    (net (code "86") (name "unconnected-(ESP32-IO42-Pad35)") (class "Default")
      (node (ref "ESP32") (pin "35") (pinfunction "IO42_35") (pintype "unspecified+no_connect"))
    )
    (net (code "87") (name "unconnected-(ESP32-IO45-Pad26)") (class "Default")
      (node (ref "ESP32") (pin "26") (pinfunction "IO45_26") (pintype "unspecified+no_connect"))
    )
    (net (code "88") (name "unconnected-(ESP32-IO46-Pad16)") (class "Default")
      (node (ref "ESP32") (pin "16") (pinfunction "IO46_16") (pintype "unspecified+no_connect"))
    )
    (net (code "89") (name "unconnected-(ESP32-IO47-Pad24)") (class "Default")
      (node (ref "ESP32") (pin "24") (pinfunction "IO47_24") (pintype "unspecified+no_connect"))
    )
    (net (code "90") (name "unconnected-(ESP32-IO48-Pad25)") (class "Default")
      (node (ref "ESP32") (pin "25") (pinfunction "IO48_25") (pintype "unspecified+no_connect"))
    )
    (net (code "91") (name "unconnected-(IRLEDREF-A-Pad1)") (class "Default")
      (node (ref "IRLEDREF") (pin "1") (pinfunction "A_1") (pintype "input+no_connect"))
    )
    (net (code "92") (name "unconnected-(IRRECREF-OUT-Pad1)") (class "Default")
      (node (ref "IRRECREF") (pin "1") (pinfunction "OUT_1") (pintype "unspecified+no_connect"))
    )
    (net (code "93") (name "unconnected-(IRRECREF-VS-Pad3)") (class "Default")
      (node (ref "IRRECREF") (pin "3") (pinfunction "VS_3") (pintype "unspecified+no_connect"))
    )
    (net (code "94") (name "unconnected-(MUX_I2C-SC6-Pad22)") (class "Default")
      (node (ref "MUX_I2C") (pin "22") (pinfunction "SC6_22") (pintype "unspecified+no_connect"))
    )
    (net (code "95") (name "unconnected-(MUX_I2C-SC7-Pad24)") (class "Default")
      (node (ref "MUX_I2C") (pin "24") (pinfunction "SC7_24") (pintype "unspecified+no_connect"))
    )
    (net (code "96") (name "unconnected-(MUX_I2C-SD6-Pad21)") (class "Default")
      (node (ref "MUX_I2C") (pin "21") (pinfunction "SD6_21") (pintype "unspecified+no_connect"))
    )
    (net (code "97") (name "unconnected-(MUX_I2C-SD7-Pad23)") (class "Default")
      (node (ref "MUX_I2C") (pin "23") (pinfunction "SD7_23") (pintype "unspecified+no_connect"))
    )
    (net (code "98") (name "unconnected-(MUX_RX-B7-Pad13)") (class "Default")
      (node (ref "MUX_RX") (pin "13") (pinfunction "B7_13") (pintype "unspecified+no_connect"))
    )
    (net (code "99") (name "unconnected-(MUX_RX-B8-Pad12)") (class "Default")
      (node (ref "MUX_RX") (pin "12") (pinfunction "B8_12") (pintype "unspecified+no_connect"))
    )
    (net (code "100") (name "unconnected-(MUX_RX-NC-Pad6)") (class "Default")
      (node (ref "MUX_RX") (pin "6") (pinfunction "NC_6") (pintype "unspecified+no_connect"))
    )
    (net (code "101") (name "unconnected-(MUX_TX-B7-Pad13)") (class "Default")
      (node (ref "MUX_TX") (pin "13") (pinfunction "B7_13") (pintype "unspecified+no_connect"))
    )
    (net (code "102") (name "unconnected-(MUX_TX-B8-Pad12)") (class "Default")
      (node (ref "MUX_TX") (pin "12") (pinfunction "B8_12") (pintype "unspecified+no_connect"))
    )
    (net (code "103") (name "unconnected-(MUX_TX-NC-Pad6)") (class "Default")
      (node (ref "MUX_TX") (pin "6") (pinfunction "NC_6") (pintype "unspecified+no_connect"))
    )
    (net (code "104") (name "unconnected-(RGB-DOUT-Pad3)") (class "Default")
      (node (ref "RGB") (pin "3") (pinfunction "DOUT_3") (pintype "unspecified+no_connect"))
    )
    (net (code "105") (name "unconnected-(RST_SW-Pad2)") (class "Default")
      (node (ref "RST_SW") (pin "2") (pinfunction "2_2") (pintype "unspecified+no_connect"))
    )
    (net (code "106") (name "unconnected-(RST_SW-Pad3)") (class "Default")
      (node (ref "RST_SW") (pin "3") (pinfunction "3_3") (pintype "unspecified+no_connect"))
    )
    (net (code "107") (name "unconnected-(TOF_REF-GND-Pad2)") (class "Default")
      (node (ref "TOF_REF") (pin "2") (pinfunction "GND_2") (pintype "unspecified+no_connect"))
    )
    (net (code "108") (name "unconnected-(TOF_REF-GPIO1-Pad5)") (class "Default")
      (node (ref "TOF_REF") (pin "5") (pinfunction "GPIO1_5") (pintype "unspecified+no_connect"))
    )
    (net (code "109") (name "unconnected-(TOF_REF-SCL-Pad3)") (class "Default")
      (node (ref "TOF_REF") (pin "3") (pinfunction "SCL_3") (pintype "unspecified+no_connect"))
    )
    (net (code "110") (name "unconnected-(TOF_REF-SDA-Pad4)") (class "Default")
      (node (ref "TOF_REF") (pin "4") (pinfunction "SDA_4") (pintype "unspecified+no_connect"))
    )
    (net (code "111") (name "unconnected-(TOF_REF-VIN-Pad1)") (class "Default")
      (node (ref "TOF_REF") (pin "1") (pinfunction "VIN_1") (pintype "unspecified+no_connect"))
    )
    (net (code "112") (name "unconnected-(TOF_REF-XSHUT-Pad6)") (class "Default")
      (node (ref "TOF_REF") (pin "6") (pinfunction "XSHUT_6") (pintype "unspecified+no_connect"))
    )
    (net (code "113") (name "unconnected-(U7-1A-Pad12)") (class "Default")
      (node (ref "U7") (pin "12") (pinfunction "1A_12") (pintype "unspecified+no_connect"))
    )
    (net (code "114") (name "unconnected-(U7-1B-Pad11)") (class "Default")
      (node (ref "U7") (pin "11") (pinfunction "1B_11") (pintype "unspecified+no_connect"))
    )
    (net (code "115") (name "unconnected-(U7-2A-Pad13)") (class "Default")
      (node (ref "U7") (pin "13") (pinfunction "2A_13") (pintype "unspecified+no_connect"))
    )
    (net (code "116") (name "unconnected-(U7-2B-Pad14)") (class "Default")
      (node (ref "U7") (pin "14") (pinfunction "2B_14") (pintype "unspecified+no_connect"))
    )
    (net (code "117") (name "unconnected-(U7-DIR-Pad8)") (class "Default")
      (node (ref "U7") (pin "8") (pinfunction "DIR_8") (pintype "unspecified+no_connect"))
    )
    (net (code "118") (name "unconnected-(U7-EN#-Pad1)") (class "Default")
      (node (ref "U7") (pin "1") (pinfunction "EN#_1") (pintype "unspecified+no_connect"))
    )
    (net (code "119") (name "unconnected-(U7-GND-Pad9)") (class "Default")
      (node (ref "U7") (pin "9") (pinfunction "GND_9") (pintype "unspecified+no_connect"))
    )
    (net (code "120") (name "unconnected-(U7-GND-Pad15)") (class "Default")
      (node (ref "U7") (pin "15") (pinfunction "GND_15") (pintype "unspecified+no_connect"))
    )
    (net (code "121") (name "unconnected-(U7-MS1-Pad2)") (class "Default")
      (node (ref "U7") (pin "2") (pinfunction "MS1_2") (pintype "unspecified+no_connect"))
    )
    (net (code "122") (name "unconnected-(U7-MS2-Pad3)") (class "Default")
      (node (ref "U7") (pin "3") (pinfunction "MS2_3") (pintype "unspecified+no_connect"))
    )
    (net (code "123") (name "unconnected-(U7-MS3-Pad4)") (class "Default")
      (node (ref "U7") (pin "4") (pinfunction "MS3_4") (pintype "unspecified+no_connect"))
    )
    (net (code "124") (name "unconnected-(U7-RST#-Pad5)") (class "Default")
      (node (ref "U7") (pin "5") (pinfunction "RST#_5") (pintype "unspecified+no_connect"))
    )
    (net (code "125") (name "unconnected-(U7-SLP#-Pad6)") (class "Default")
      (node (ref "U7") (pin "6") (pinfunction "SLP#_6") (pintype "unspecified+no_connect"))
    )
    (net (code "126") (name "unconnected-(U7-STEP-Pad7)") (class "Default")
      (node (ref "U7") (pin "7") (pinfunction "STEP_7") (pintype "unspecified+no_connect"))
    )
    (net (code "127") (name "unconnected-(U7-VDD-Pad10)") (class "Default")
      (node (ref "U7") (pin "10") (pinfunction "VDD_10") (pintype "unspecified+no_connect"))
    )
    (net (code "128") (name "unconnected-(U7-VMOT-Pad16)") (class "Default")
      (node (ref "U7") (pin "16") (pinfunction "VMOT_16") (pintype "unspecified+no_connect"))
    )
    (net (code "129") (name "unconnected-(USB-EP-Pad6)") (class "Default")
      (node (ref "USB") (pin "6") (pinfunction "EP_6") (pintype "unspecified+no_connect"))
    )
    (net (code "130") (name "unconnected-(USB-EP-Pad7)") (class "Default")
      (node (ref "USB") (pin "7") (pinfunction "EP_7") (pintype "unspecified+no_connect"))
    )
    (net (code "131") (name "unconnected-(USB-EP-Pad8)") (class "Default")
      (node (ref "USB") (pin "8") (pinfunction "EP_8") (pintype "unspecified+no_connect"))
    )
    (net (code "132") (name "unconnected-(USB-EP-Pad9)") (class "Default")
      (node (ref "USB") (pin "9") (pinfunction "EP_9") (pintype "unspecified+no_connect"))
    )
    (net (code "133") (name "unconnected-(USB-ID-Pad4)") (class "Default")
      (node (ref "USB") (pin "4") (pinfunction "ID_4") (pintype "unspecified+no_connect"))
    )
    (net (code "134") (name "unconnected-(USB2UART-CHR0-Pad15)") (class "Default")
      (node (ref "USB2UART") (pin "15") (pinfunction "CHR0_15") (pintype "unspecified+no_connect"))
    )
    (net (code "135") (name "unconnected-(USB2UART-CHR1-Pad14)") (class "Default")
      (node (ref "USB2UART") (pin "14") (pinfunction "CHR1_14") (pintype "unspecified+no_connect"))
    )
    (net (code "136") (name "unconnected-(USB2UART-CHREN-Pad13)") (class "Default")
      (node (ref "USB2UART") (pin "13") (pinfunction "CHREN_13") (pintype "unspecified+no_connect"))
    )
    (net (code "137") (name "unconnected-(USB2UART-CTS-Pad23)") (class "Default")
      (node (ref "USB2UART") (pin "23") (pinfunction "CTS_23") (pintype "unspecified+no_connect"))
    )
    (net (code "138") (name "unconnected-(USB2UART-DCD-Pad1)") (class "Default")
      (node (ref "USB2UART") (pin "1") (pinfunction "DCD_1") (pintype "unspecified+no_connect"))
    )
    (net (code "139") (name "unconnected-(USB2UART-DSR-Pad27)") (class "Default")
      (node (ref "USB2UART") (pin "27") (pinfunction "DSR_27") (pintype "unspecified+no_connect"))
    )
    (net (code "140") (name "unconnected-(USB2UART-DTR-Pad28)") (class "Default")
      (node (ref "USB2UART") (pin "28") (pinfunction "DTR_28") (pintype "unspecified+no_connect"))
    )
    (net (code "141") (name "unconnected-(USB2UART-GPIO.0{slash}TXT-Pad19)") (class "Default")
      (node (ref "USB2UART") (pin "19") (pinfunction "GPIO.0/TXT_19") (pintype "unspecified+no_connect"))
    )
    (net (code "142") (name "unconnected-(USB2UART-GPIO.1{slash}RXT-Pad18)") (class "Default")
      (node (ref "USB2UART") (pin "18") (pinfunction "GPIO.1/RXT_18") (pintype "unspecified+no_connect"))
    )
    (net (code "143") (name "unconnected-(USB2UART-GPIO.2{slash}RS485-Pad17)") (class "Default")
      (node (ref "USB2UART") (pin "17") (pinfunction "GPIO.2/RS485_17") (pintype "unspecified+no_connect"))
    )
    (net (code "144") (name "unconnected-(USB2UART-GPIO.3{slash}WAKEUP-Pad16)") (class "Default")
      (node (ref "USB2UART") (pin "16") (pinfunction "GPIO.3/WAKEUP_16") (pintype "unspecified+no_connect"))
    )
    (net (code "145") (name "unconnected-(USB2UART-GPIO.4-Pad22)") (class "Default")
      (node (ref "USB2UART") (pin "22") (pinfunction "GPIO.4_22") (pintype "unspecified+no_connect"))
    )
    (net (code "146") (name "unconnected-(USB2UART-GPIO.5-Pad21)") (class "Default")
      (node (ref "USB2UART") (pin "21") (pinfunction "GPIO.5_21") (pintype "unspecified+no_connect"))
    )
    (net (code "147") (name "unconnected-(USB2UART-GPIO.6-Pad20)") (class "Default")
      (node (ref "USB2UART") (pin "20") (pinfunction "GPIO.6_20") (pintype "unspecified+no_connect"))
    )
    (net (code "148") (name "unconnected-(USB2UART-NC-Pad10)") (class "Default")
      (node (ref "USB2UART") (pin "10") (pinfunction "NC_10") (pintype "unspecified+no_connect"))
    )
    (net (code "149") (name "unconnected-(USB2UART-RI{slash}CLK-Pad2)") (class "Default")
      (node (ref "USB2UART") (pin "2") (pinfunction "RI/CLK_2") (pintype "unspecified+no_connect"))
    )
    (net (code "150") (name "unconnected-(USB2UART-RTS-Pad24)") (class "Default")
      (node (ref "USB2UART") (pin "24") (pinfunction "RTS_24") (pintype "unspecified+no_connect"))
    )
    (net (code "151") (name "unconnected-(USB2UART-SUSPEND-Pad12)") (class "Default")
      (node (ref "USB2UART") (pin "12") (pinfunction "SUSPEND_12") (pintype "unspecified+no_connect"))
    )
    (net (code "152") (name "unconnected-(USB2UART-SUSPENDb-Pad11)") (class "Default")
      (node (ref "USB2UART") (pin "11") (pinfunction "SUSPENDb_11") (pintype "unspecified+no_connect"))
    )
  )
)
